# Motor.net
KiCad netlist of a schematic drawn in Altium Designer
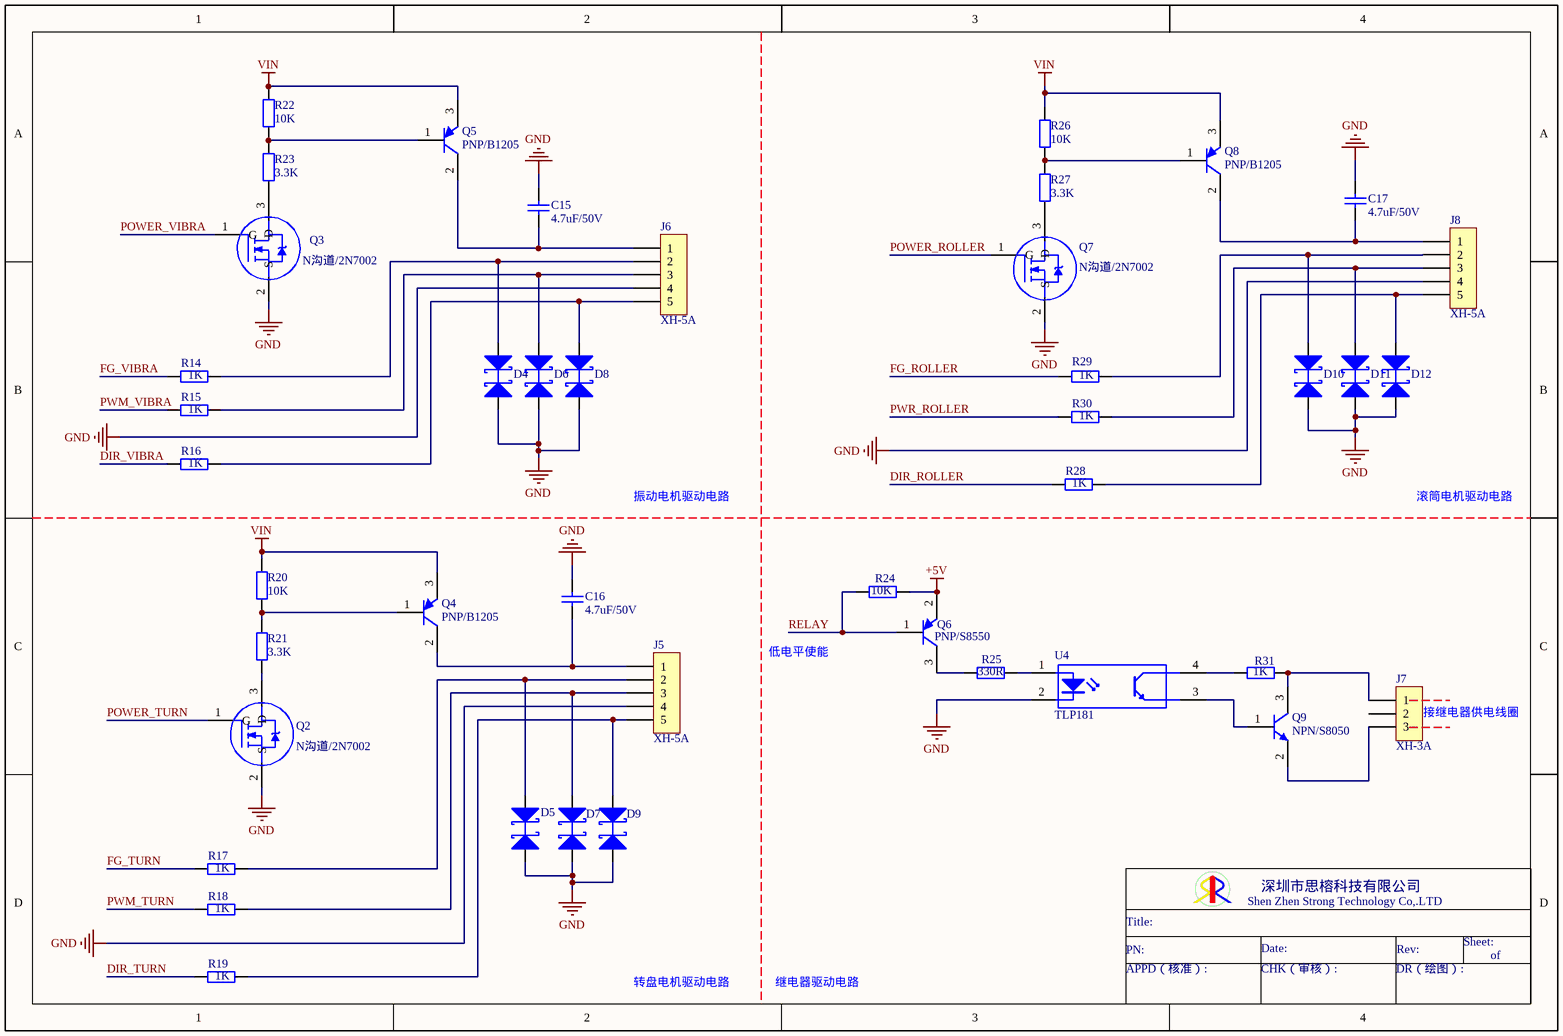
[diagram p0: Motor.SchDoc]

(export (version "E")
  (design (tool "Eeschema 10.0.6"))
  (components
    (comp (ref "C15")
      (value "4.7uF/50V")
      (footprint "0603C")
      (description "瓷片电容,4.7uF,5%,X7R,50V,0603")
      (libsource (lib "SR SCH Library V02") (part "C4.7uF-0603"))
    )
    (comp (ref "C16")
      (value "4.7uF/50V")
      (footprint "0603C")
      (description "瓷片电容,4.7uF,5%,X7R,50V,0603")
      (libsource (lib "SR SCH Library V02") (part "C4.7uF-0603"))
    )
    (comp (ref "C17")
      (value "4.7uF/50V")
      (footprint "0603C")
      (description "瓷片电容,4.7uF,5%,X7R,50V,0603")
      (libsource (lib "SR SCH Library V02") (part "C4.7uF-0603"))
    )
    (comp (ref "D4")
      (value "ESD5B5.0ST1G")
      (footprint "SOD-523")
      (description "TVS管,5V,SOD-523")
      (libsource (lib "SR SCH Library V02") (part "ESD5B5.0ST1G"))
    )
    (comp (ref "D5")
      (value "ESD5B5.0ST1G")
      (footprint "SOD-523")
      (description "TVS管,5V,SOD-523")
      (libsource (lib "SR SCH Library V02") (part "ESD5B5.0ST1G"))
    )
    (comp (ref "D6")
      (value "ESD5B5.0ST1G")
      (footprint "SOD-523")
      (description "TVS管,5V,SOD-523")
      (libsource (lib "SR SCH Library V02") (part "ESD5B5.0ST1G"))
    )
    (comp (ref "D7")
      (value "ESD5B5.0ST1G")
      (footprint "SOD-523")
      (description "TVS管,5V,SOD-523")
      (libsource (lib "SR SCH Library V02") (part "ESD5B5.0ST1G"))
    )
    (comp (ref "D8")
      (value "ESD5B5.0ST1G")
      (footprint "SOD-523")
      (description "TVS管,5V,SOD-523")
      (libsource (lib "SR SCH Library V02") (part "ESD5B5.0ST1G"))
    )
    (comp (ref "D9")
      (value "ESD5B5.0ST1G")
      (footprint "SOD-523")
      (description "TVS管,5V,SOD-523")
      (libsource (lib "SR SCH Library V02") (part "ESD5B5.0ST1G"))
    )
    (comp (ref "D10")
      (value "ESD5B5.0ST1G")
      (footprint "SOD-523")
      (description "TVS管,5V,SOD-523")
      (libsource (lib "SR SCH Library V02") (part "ESD5B5.0ST1G"))
    )
    (comp (ref "D11")
      (value "ESD5B5.0ST1G")
      (footprint "SOD-523")
      (description "TVS管,5V,SOD-523")
      (libsource (lib "SR SCH Library V02") (part "ESD5B5.0ST1G"))
    )
    (comp (ref "D12")
      (value "ESD5B5.0ST1G")
      (footprint "SOD-523")
      (description "TVS管,5V,SOD-523")
      (libsource (lib "SR SCH Library V02") (part "ESD5B5.0ST1G"))
    )
    (comp (ref "J5")
      (value "XH-5A")
      (footprint "CN5-2.54")
      (description "CONN,XH-5A,5PIN,2.54mm插座")
      (libsource (lib "SR SCH Library V02") (part "CONN-XH-5A"))
    )
    (comp (ref "J6")
      (value "XH-5A")
      (footprint "CN5-2.54")
      (description "CONN,XH-5A,5PIN,2.54mm插座")
      (libsource (lib "SR SCH Library V02") (part "CONN-XH-5A"))
    )
    (comp (ref "J7")
      (value "XH-3A")
      (footprint "CN3-2.54")
      (description "CONN,XH-3A,3PIN,2.54mm插座")
      (libsource (lib "SR SCH Library V02") (part "CONN-XH-3A"))
    )
    (comp (ref "J8")
      (value "XH-5A")
      (footprint "CN5-2.54")
      (description "CONN,XH-5A,5PIN,2.54mm插座")
      (libsource (lib "SR SCH Library V02") (part "CONN-XH-5A"))
    )
    (comp (ref "Q2")
      (value "N沟道/2N7002")
      (footprint "SOT-23")
      (description "N沟道场效应管，2N7002，SOT-23")
      (libsource (lib "SR SCH Library V02") (part "2N7002"))
    )
    (comp (ref "Q3")
      (value "N沟道/2N7002")
      (footprint "SOT-23")
      (description "N沟道场效应管，2N7002，SOT-23")
      (libsource (lib "SR SCH Library V02") (part "2N7002"))
    )
    (comp (ref "Q4")
      (value "PNP/B1205")
      (footprint "TO-252")
      (description "PNP型三极管，B1205，SOT－23")
      (libsource (lib "Next_SCHlib") (part "B1205"))
    )
    (comp (ref "Q5")
      (value "PNP/B1205")
      (footprint "TO-252")
      (description "PNP型三极管，B1205，SOT－23")
      (libsource (lib "Next_SCHlib") (part "B1205"))
    )
    (comp (ref "Q6")
      (value "PNP/S8550")
      (footprint "SOT-23")
      (description "PNP型三极管，S8550，SOT－23")
      (libsource (lib "SR SCH Library V02") (part "S8550"))
    )
    (comp (ref "Q7")
      (value "N沟道/2N7002")
      (footprint "SOT-23")
      (description "N沟道场效应管，2N7002，SOT-23")
      (libsource (lib "SR SCH Library V02") (part "2N7002"))
    )
    (comp (ref "Q8")
      (value "PNP/B1205")
      (footprint "TO-252")
      (description "PNP型三极管，B1205，SOT－23")
      (libsource (lib "Next_SCHlib") (part "B1205"))
    )
    (comp (ref "Q9")
      (value "NPN/S8050")
      (footprint "TO-92MOD")
      (description "NPN型三极管，S8050，SOT－23")
      (libsource (lib "SR SCH Library V02") (part "S8050"))
    )
    (comp (ref "R14")
      (value "1K")
      (footprint "0603R")
      (description "金属膜电阻,1K,1%,1/10W,0603")
      (libsource (lib "SR SCH Library V02") (part "R1K-0603"))
    )
    (comp (ref "R15")
      (value "1K")
      (footprint "0603R")
      (description "金属膜电阻,1K,1%,1/10W,0603")
      (libsource (lib "SR SCH Library V02") (part "R1K-0603"))
    )
    (comp (ref "R16")
      (value "1K")
      (footprint "0603R")
      (description "金属膜电阻,1K,1%,1/10W,0603")
      (libsource (lib "SR SCH Library V02") (part "R1K-0603"))
    )
    (comp (ref "R17")
      (value "1K")
      (footprint "0603R")
      (description "金属膜电阻,1K,1%,1/10W,0603")
      (libsource (lib "SR SCH Library V02") (part "R1K-0603"))
    )
    (comp (ref "R18")
      (value "1K")
      (footprint "0603R")
      (description "金属膜电阻,1K,1%,1/10W,0603")
      (libsource (lib "SR SCH Library V02") (part "R1K-0603"))
    )
    (comp (ref "R19")
      (value "1K")
      (footprint "0603R")
      (description "金属膜电阻,1K,1%,1/10W,0603")
      (libsource (lib "SR SCH Library V02") (part "R1K-0603"))
    )
    (comp (ref "R20")
      (value "10K")
      (footprint "0603R")
      (description "金属膜电阻,10K,1%,1/10W,0603")
      (libsource (lib "SR SCH Library V02") (part "R10K-0603"))
    )
    (comp (ref "R21")
      (value "3.3K")
      (footprint "0805R")
      (description "金属膜电阻,3.3K,1%,1/10W,0603")
      (libsource (lib "SR SCH Library V02") (part "R3.3K-0603"))
    )
    (comp (ref "R22")
      (value "10K")
      (footprint "0603R")
      (description "金属膜电阻,10K,1%,1/10W,0603")
      (libsource (lib "") (part "R10K-0603_1"))
    )
    (comp (ref "R23")
      (value "3.3K")
      (footprint "0805R")
      (description "金属膜电阻,3.3K,1%,1/10W,0603")
      (libsource (lib "SR SCH Library V02") (part "R3.3K-0603"))
    )
    (comp (ref "R24")
      (value "10K")
      (footprint "0603R")
      (description "金属膜电阻,10K,1%,1/10W,0603")
      (libsource (lib "") (part "R10K-0603_2"))
    )
    (comp (ref "R25")
      (value "330R")
      (footprint "0603R")
      (description "金属膜电阻,330R,1%,1/10W,0603")
      (libsource (lib "SR SCH Library V02") (part "R33R-0805"))
    )
    (comp (ref "R26")
      (value "10K")
      (footprint "0603R")
      (description "金属膜电阻,10K,1%,1/10W,0603")
      (libsource (lib "SR SCH Library V02") (part "R10K-0603"))
    )
    (comp (ref "R27")
      (value "3.3K")
      (footprint "0805R")
      (description "金属膜电阻,3.3K,1%,1/10W,0603")
      (libsource (lib "SR SCH Library V02") (part "R3.3K-0603"))
    )
    (comp (ref "R28")
      (value "1K")
      (footprint "0603R")
      (description "金属膜电阻,1K,1%,1/10W,0603")
      (libsource (lib "SR SCH Library V02") (part "R1K-0603"))
    )
    (comp (ref "R29")
      (value "1K")
      (footprint "0603R")
      (description "金属膜电阻,1K,1%,1/10W,0603")
      (libsource (lib "SR SCH Library V02") (part "R1K-0603"))
    )
    (comp (ref "R30")
      (value "1K")
      (footprint "0603R")
      (description "金属膜电阻,1K,1%,1/10W,0603")
      (libsource (lib "SR SCH Library V02") (part "R1K-0603"))
    )
    (comp (ref "R31")
      (value "1K")
      (footprint "0603R")
      (description "金属膜电阻,1K,1%,1/10W,0603")
      (libsource (lib "SR SCH Library V02") (part "R1K-0603"))
    )
    (comp (ref "U4")
      (value "TLP181")
      (footprint "SOP4-2.54")
      (description "光耦，TLP181，SOP4")
      (libsource (lib "SR SCH Library V02") (part "TLP181"))
    )
  )
  (nets
    (net (code "1") (name "+5V") (class "Default")
      (node (ref "Q6") (pin "2") (pinfunction "E_2") (pintype "passive"))
      (node (ref "R24") (pin "1") (pinfunction "1_1") (pintype "passive"))
    )
    (net (code "2") (name "/DIR_ROLLER") (class "Default")
      (node (ref "R28") (pin "1") (pinfunction "1_1") (pintype "passive"))
    )
    (net (code "3") (name "/DIR_TURN") (class "Default")
      (node (ref "R19") (pin "1") (pinfunction "1_1") (pintype "passive"))
    )
    (net (code "4") (name "/DIR_VIBRA") (class "Default")
      (node (ref "R16") (pin "1") (pinfunction "1_1") (pintype "passive"))
    )
    (net (code "5") (name "/FG_ROLLER") (class "Default")
      (node (ref "R29") (pin "1") (pinfunction "1_1") (pintype "passive"))
    )
    (net (code "6") (name "/FG_TURN") (class "Default")
      (node (ref "R17") (pin "1") (pinfunction "1_1") (pintype "passive"))
    )
    (net (code "7") (name "/FG_VIBRA") (class "Default")
      (node (ref "R14") (pin "1") (pinfunction "1_1") (pintype "passive"))
    )
    (net (code "8") (name "/POWER_ROLLER") (class "Default")
      (node (ref "Q7") (pin "1") (pinfunction "G_1") (pintype "passive"))
    )
    (net (code "9") (name "/POWER_TURN") (class "Default")
      (node (ref "Q2") (pin "1") (pinfunction "G_1") (pintype "passive"))
    )
    (net (code "10") (name "/POWER_VIBRA") (class "Default")
      (node (ref "Q3") (pin "1") (pinfunction "G_1") (pintype "passive"))
    )
    (net (code "11") (name "/PWM_TURN") (class "Default")
      (node (ref "R18") (pin "1") (pinfunction "1_1") (pintype "passive"))
    )
    (net (code "12") (name "/PWM_VIBRA") (class "Default")
      (node (ref "R15") (pin "1") (pinfunction "1_1") (pintype "passive"))
    )
    (net (code "13") (name "/PWR_ROLLER") (class "Default")
      (node (ref "R30") (pin "1") (pinfunction "1_1") (pintype "passive"))
    )
    (net (code "14") (name "/RELAY") (class "Default")
      (node (ref "Q6") (pin "1") (pinfunction "B_1") (pintype "passive"))
      (node (ref "R24") (pin "2") (pinfunction "2_2") (pintype "passive"))
    )
    (net (code "15") (name "GND") (class "Default")
      (node (ref "C15") (pin "2") (pinfunction "2_2") (pintype "passive"))
      (node (ref "C16") (pin "2") (pinfunction "2_2") (pintype "passive"))
      (node (ref "C17") (pin "2") (pinfunction "2_2") (pintype "passive"))
      (node (ref "D10") (pin "2") (pinfunction "2_2") (pintype "passive"))
      (node (ref "D11") (pin "2") (pinfunction "2_2") (pintype "passive"))
      (node (ref "D12") (pin "2") (pinfunction "2_2") (pintype "passive"))
      (node (ref "D4") (pin "2") (pinfunction "2_2") (pintype "passive"))
      (node (ref "D5") (pin "2") (pinfunction "2_2") (pintype "passive"))
      (node (ref "D6") (pin "2") (pinfunction "2_2") (pintype "passive"))
      (node (ref "D7") (pin "2") (pinfunction "2_2") (pintype "passive"))
      (node (ref "D8") (pin "2") (pinfunction "2_2") (pintype "passive"))
      (node (ref "D9") (pin "2") (pinfunction "2_2") (pintype "passive"))
      (node (ref "J5") (pin "4") (pinfunction "4_4") (pintype "passive"))
      (node (ref "J6") (pin "4") (pinfunction "4_4") (pintype "passive"))
      (node (ref "J8") (pin "4") (pinfunction "4_4") (pintype "passive"))
      (node (ref "Q2") (pin "2") (pinfunction "S_2") (pintype "passive"))
      (node (ref "Q3") (pin "2") (pinfunction "S_2") (pintype "passive"))
      (node (ref "Q7") (pin "2") (pinfunction "S_2") (pintype "passive"))
      (node (ref "U4") (pin "2") (pinfunction "K_2") (pintype "passive"))
    )
    (net (code "16") (name "Net-(D4-Pad1)") (class "Default")
      (node (ref "D4") (pin "1") (pinfunction "1_1") (pintype "passive"))
      (node (ref "J6") (pin "2") (pinfunction "2_2") (pintype "passive"))
      (node (ref "R14") (pin "2") (pinfunction "2_2") (pintype "passive"))
    )
    (net (code "17") (name "Net-(D5-Pad1)") (class "Default")
      (node (ref "D5") (pin "1") (pinfunction "1_1") (pintype "passive"))
      (node (ref "J5") (pin "2") (pinfunction "2_2") (pintype "passive"))
      (node (ref "R17") (pin "2") (pinfunction "2_2") (pintype "passive"))
    )
    (net (code "18") (name "Net-(D6-Pad1)") (class "Default")
      (node (ref "D6") (pin "1") (pinfunction "1_1") (pintype "passive"))
      (node (ref "J6") (pin "3") (pinfunction "3_3") (pintype "passive"))
      (node (ref "R15") (pin "2") (pinfunction "2_2") (pintype "passive"))
    )
    (net (code "19") (name "Net-(D7-Pad1)") (class "Default")
      (node (ref "D7") (pin "1") (pinfunction "1_1") (pintype "passive"))
      (node (ref "J5") (pin "3") (pinfunction "3_3") (pintype "passive"))
      (node (ref "R18") (pin "2") (pinfunction "2_2") (pintype "passive"))
    )
    (net (code "20") (name "Net-(D8-Pad1)") (class "Default")
      (node (ref "D8") (pin "1") (pinfunction "1_1") (pintype "passive"))
      (node (ref "J6") (pin "5") (pinfunction "5_5") (pintype "passive"))
      (node (ref "R16") (pin "2") (pinfunction "2_2") (pintype "passive"))
    )
    (net (code "21") (name "Net-(D9-Pad1)") (class "Default")
      (node (ref "D9") (pin "1") (pinfunction "1_1") (pintype "passive"))
      (node (ref "J5") (pin "5") (pinfunction "5_5") (pintype "passive"))
      (node (ref "R19") (pin "2") (pinfunction "2_2") (pintype "passive"))
    )
    (net (code "22") (name "Net-(D10-Pad1)") (class "Default")
      (node (ref "D10") (pin "1") (pinfunction "1_1") (pintype "passive"))
      (node (ref "J8") (pin "2") (pinfunction "2_2") (pintype "passive"))
      (node (ref "R29") (pin "2") (pinfunction "2_2") (pintype "passive"))
    )
    (net (code "23") (name "Net-(D11-Pad1)") (class "Default")
      (node (ref "D11") (pin "1") (pinfunction "1_1") (pintype "passive"))
      (node (ref "J8") (pin "3") (pinfunction "3_3") (pintype "passive"))
      (node (ref "R30") (pin "2") (pinfunction "2_2") (pintype "passive"))
    )
    (net (code "24") (name "Net-(D12-Pad1)") (class "Default")
      (node (ref "D12") (pin "1") (pinfunction "1_1") (pintype "passive"))
      (node (ref "J8") (pin "5") (pinfunction "5_5") (pintype "passive"))
      (node (ref "R28") (pin "2") (pinfunction "2_2") (pintype "passive"))
    )
    (net (code "25") (name "Net-(Q2-D)") (class "Default")
      (node (ref "Q2") (pin "3") (pinfunction "D_3") (pintype "passive"))
      (node (ref "R21") (pin "1") (pinfunction "1_1") (pintype "passive"))
    )
    (net (code "26") (name "Net-(Q3-D)") (class "Default")
      (node (ref "Q3") (pin "3") (pinfunction "D_3") (pintype "passive"))
      (node (ref "R23") (pin "1") (pinfunction "1_1") (pintype "passive"))
    )
    (net (code "27") (name "Net-(Q4-B)") (class "Default")
      (node (ref "Q4") (pin "1") (pinfunction "B_1") (pintype "passive"))
      (node (ref "R20") (pin "2") (pinfunction "2_2") (pintype "passive"))
      (node (ref "R21") (pin "2") (pinfunction "2_2") (pintype "passive"))
    )
    (net (code "28") (name "Net-(Q4-C)") (class "Default")
      (node (ref "C16") (pin "1") (pinfunction "1_1") (pintype "passive"))
      (node (ref "J5") (pin "1") (pinfunction "1_1") (pintype "passive"))
      (node (ref "Q4") (pin "2") (pinfunction "C_2") (pintype "passive"))
    )
    (net (code "29") (name "Net-(Q5-B)") (class "Default")
      (node (ref "Q5") (pin "1") (pinfunction "B_1") (pintype "passive"))
      (node (ref "R22") (pin "1") (pinfunction "1_1") (pintype "passive"))
      (node (ref "R23") (pin "2") (pinfunction "2_2") (pintype "passive"))
    )
    (net (code "30") (name "Net-(Q5-C)") (class "Default")
      (node (ref "C15") (pin "1") (pinfunction "1_1") (pintype "passive"))
      (node (ref "J6") (pin "1") (pinfunction "1_1") (pintype "passive"))
      (node (ref "Q5") (pin "2") (pinfunction "C_2") (pintype "passive"))
    )
    (net (code "31") (name "Net-(Q6-C)") (class "Default")
      (node (ref "Q6") (pin "3") (pinfunction "C_3") (pintype "passive"))
      (node (ref "R25") (pin "1") (pinfunction "1_1") (pintype "passive"))
    )
    (net (code "32") (name "Net-(Q7-D)") (class "Default")
      (node (ref "Q7") (pin "3") (pinfunction "D_3") (pintype "passive"))
      (node (ref "R27") (pin "1") (pinfunction "1_1") (pintype "passive"))
    )
    (net (code "33") (name "Net-(Q8-B)") (class "Default")
      (node (ref "Q8") (pin "1") (pinfunction "B_1") (pintype "passive"))
      (node (ref "R26") (pin "2") (pinfunction "2_2") (pintype "passive"))
      (node (ref "R27") (pin "2") (pinfunction "2_2") (pintype "passive"))
    )
    (net (code "34") (name "Net-(Q8-C)") (class "Default")
      (node (ref "C17") (pin "1") (pinfunction "1_1") (pintype "passive"))
      (node (ref "J8") (pin "1") (pinfunction "1_1") (pintype "passive"))
      (node (ref "Q8") (pin "2") (pinfunction "C_2") (pintype "passive"))
    )
    (net (code "35") (name "Net-(Q9-B)") (class "Default")
      (node (ref "Q9") (pin "1") (pinfunction "B_1") (pintype "passive"))
      (node (ref "U4") (pin "3") (pinfunction "E_3") (pintype "passive"))
    )
    (net (code "36") (name "Net-(Q9-C)") (class "Default")
      (node (ref "J7") (pin "1") (pinfunction "1_1") (pintype "passive"))
      (node (ref "Q9") (pin "3") (pinfunction "C_3") (pintype "passive"))
      (node (ref "R31") (pin "2") (pinfunction "2_2") (pintype "passive"))
    )
    (net (code "37") (name "Net-(Q9-E)") (class "Default")
      (node (ref "J7") (pin "3") (pinfunction "3_3") (pintype "passive"))
      (node (ref "Q9") (pin "2") (pinfunction "E_2") (pintype "passive"))
    )
    (net (code "38") (name "Net-(U4-A)") (class "Default")
      (node (ref "R25") (pin "2") (pinfunction "2_2") (pintype "passive"))
      (node (ref "U4") (pin "1") (pinfunction "A_1") (pintype "passive"))
    )
    (net (code "39") (name "Net-(U4-C)") (class "Default")
      (node (ref "R31") (pin "1") (pinfunction "1_1") (pintype "passive"))
      (node (ref "U4") (pin "4") (pinfunction "C_4") (pintype "passive"))
    )
    (net (code "40") (name "VIN") (class "Default")
      (node (ref "Q4") (pin "3") (pinfunction "E_3") (pintype "passive"))
      (node (ref "Q5") (pin "3") (pinfunction "E_3") (pintype "passive"))
      (node (ref "Q8") (pin "3") (pinfunction "E_3") (pintype "passive"))
      (node (ref "R20") (pin "1") (pinfunction "1_1") (pintype "passive"))
      (node (ref "R22") (pin "2") (pinfunction "2_2") (pintype "passive"))
      (node (ref "R26") (pin "1") (pinfunction "1_1") (pintype "passive"))
    )
    (net (code "41") (name "unconnected-(J7-Pad2)") (class "Default")
      (node (ref "J7") (pin "2") (pinfunction "2_2") (pintype "passive"))
    )
  )
)
